# PGTNXEN_gate_out.net
KiCad netlist of a schematic drawn in EAGLE
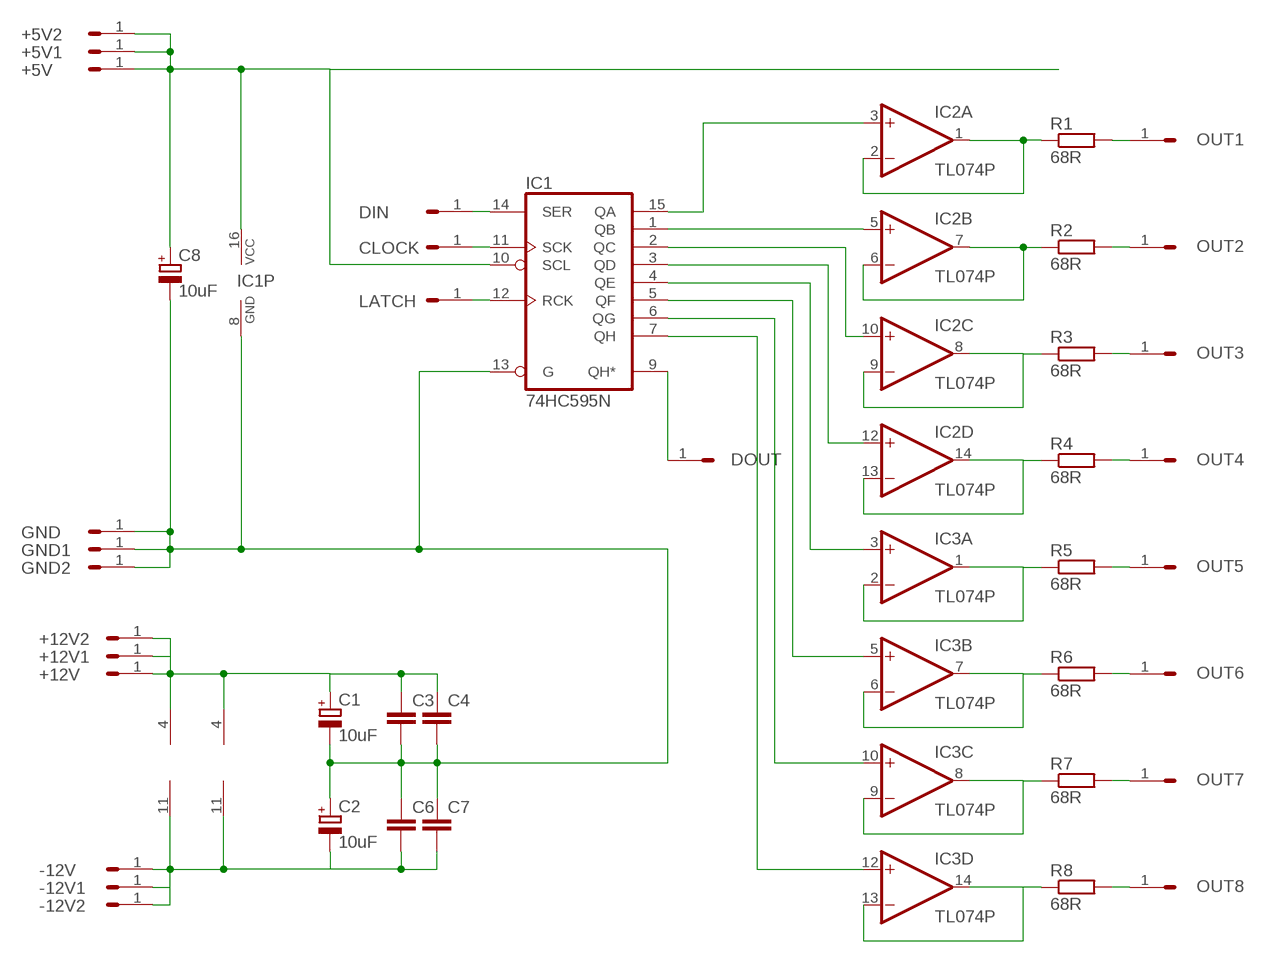
[diagram p0: schematic, sheet 1]

(export (version "E")
  (design (tool "Eeschema 10.0.6"))
  (components
    (comp (ref "+5V")
      (value "HEADER/MALE/01")
      (footprint "eagle-import:HEADER_MALE_01")
      (libsource (lib "eagle-import") (part "HEADER/MALE/01"))
    )
    (comp (ref "+5V1")
      (value "HEADER/MALE/01")
      (footprint "eagle-import:HEADER_MALE_01")
      (libsource (lib "eagle-import") (part "HEADER/MALE/01"))
    )
    (comp (ref "+5V2")
      (value "HEADER/MALE/01")
      (footprint "eagle-import:HEADER_MALE_01")
      (libsource (lib "eagle-import") (part "HEADER/MALE/01"))
    )
    (comp (ref "+12V")
      (value "HEADER/MALE/01")
      (footprint "eagle-import:HEADER_MALE_01")
      (libsource (lib "eagle-import") (part "HEADER/MALE/01"))
    )
    (comp (ref "+12V1")
      (value "HEADER/MALE/01")
      (footprint "eagle-import:HEADER_MALE_01")
      (libsource (lib "eagle-import") (part "HEADER/MALE/01"))
    )
    (comp (ref "+12V2")
      (value "HEADER/MALE/01")
      (footprint "eagle-import:HEADER_MALE_01")
      (libsource (lib "eagle-import") (part "HEADER/MALE/01"))
    )
    (comp (ref "-12V")
      (value "HEADER/MALE/01")
      (footprint "eagle-import:HEADER_MALE_01")
      (libsource (lib "eagle-import") (part "HEADER/MALE/01"))
    )
    (comp (ref "-12V1")
      (value "HEADER/MALE/01")
      (footprint "eagle-import:HEADER_MALE_01")
      (libsource (lib "eagle-import") (part "HEADER/MALE/01"))
    )
    (comp (ref "-12V2")
      (value "HEADER/MALE/01")
      (footprint "eagle-import:HEADER_MALE_01")
      (libsource (lib "eagle-import") (part "HEADER/MALE/01"))
    )
    (comp (ref "C1")
      (value "10uF")
      (footprint "eagle-import:E2,5-6")
      (libsource (lib "eagle-import") (part "CAPACITOR/POLARIZEDE2.5-6"))
    )
    (comp (ref "C2")
      (value "10uF")
      (footprint "eagle-import:E2,5-6")
      (libsource (lib "eagle-import") (part "CAPACITOR/POLARIZEDE2.5-6"))
    )
    (comp (ref "C3")
      (value "CAPACITORCERAMICDISC/5")
      (footprint "eagle-import:CERAMICDISC_5")
      (libsource (lib "eagle-import") (part "CAPACITORCERAMICDISC/5"))
    )
    (comp (ref "C4")
      (value "CAPACITORCERAMICDISC/5")
      (footprint "eagle-import:CERAMICDISC_5")
      (libsource (lib "eagle-import") (part "CAPACITORCERAMICDISC/5"))
    )
    (comp (ref "C6")
      (value "CAPACITORCERAMICDISC/5")
      (footprint "eagle-import:CERAMICDISC_5")
      (libsource (lib "eagle-import") (part "CAPACITORCERAMICDISC/5"))
    )
    (comp (ref "C7")
      (value "CAPACITORCERAMICDISC/5")
      (footprint "eagle-import:CERAMICDISC_5")
      (libsource (lib "eagle-import") (part "CAPACITORCERAMICDISC/5"))
    )
    (comp (ref "C8")
      (value "10uF")
      (footprint "eagle-import:E2,5-6")
      (libsource (lib "eagle-import") (part "CAPACITOR/POLARIZEDE2.5-6"))
    )
    (comp (ref "CLOCK")
      (value "HEADER/MALE/01")
      (footprint "eagle-import:HEADER_MALE_01")
      (libsource (lib "eagle-import") (part "HEADER/MALE/01"))
    )
    (comp (ref "DIN")
      (value "HEADER/MALE/01")
      (footprint "eagle-import:HEADER_MALE_01")
      (libsource (lib "eagle-import") (part "HEADER/MALE/01"))
    )
    (comp (ref "DOUT")
      (value "HEADER/MALE/01")
      (footprint "eagle-import:HEADER_MALE_01")
      (libsource (lib "eagle-import") (part "HEADER/MALE/01"))
    )
    (comp (ref "GND")
      (value "HEADER/MALE/01")
      (footprint "eagle-import:HEADER_MALE_01")
      (libsource (lib "eagle-import") (part "HEADER/MALE/01"))
    )
    (comp (ref "GND1")
      (value "HEADER/MALE/01")
      (footprint "eagle-import:HEADER_MALE_01")
      (libsource (lib "eagle-import") (part "HEADER/MALE/01"))
    )
    (comp (ref "GND2")
      (value "HEADER/MALE/01")
      (footprint "eagle-import:HEADER_MALE_01")
      (libsource (lib "eagle-import") (part "HEADER/MALE/01"))
    )
    (comp (ref "IC1")
      (value "74HC595N")
      (footprint "eagle-import:DIL16")
      (libsource (lib "eagle-import") (part "74595NHC"))
    )
    (comp (ref "IC2")
      (value "TL074P")
      (footprint "eagle-import:DIL14")
      (libsource (lib "eagle-import") (part "TL074P"))
    )
    (comp (ref "IC3")
      (value "TL074P")
      (footprint "eagle-import:DIL14")
      (libsource (lib "eagle-import") (part "TL074P"))
    )
    (comp (ref "LATCH")
      (value "HEADER/MALE/01")
      (footprint "eagle-import:HEADER_MALE_01")
      (libsource (lib "eagle-import") (part "HEADER/MALE/01"))
    )
    (comp (ref "OUT1")
      (value "HEADER/MALE/01")
      (footprint "eagle-import:HEADER_MALE_01")
      (libsource (lib "eagle-import") (part "HEADER/MALE/01"))
    )
    (comp (ref "OUT2")
      (value "HEADER/MALE/01")
      (footprint "eagle-import:HEADER_MALE_01")
      (libsource (lib "eagle-import") (part "HEADER/MALE/01"))
    )
    (comp (ref "OUT3")
      (value "HEADER/MALE/01")
      (footprint "eagle-import:HEADER_MALE_01")
      (libsource (lib "eagle-import") (part "HEADER/MALE/01"))
    )
    (comp (ref "OUT4")
      (value "HEADER/MALE/01")
      (footprint "eagle-import:HEADER_MALE_01")
      (libsource (lib "eagle-import") (part "HEADER/MALE/01"))
    )
    (comp (ref "OUT5")
      (value "HEADER/MALE/01")
      (footprint "eagle-import:HEADER_MALE_01")
      (libsource (lib "eagle-import") (part "HEADER/MALE/01"))
    )
    (comp (ref "OUT6")
      (value "HEADER/MALE/01")
      (footprint "eagle-import:HEADER_MALE_01")
      (libsource (lib "eagle-import") (part "HEADER/MALE/01"))
    )
    (comp (ref "OUT7")
      (value "HEADER/MALE/01")
      (footprint "eagle-import:HEADER_MALE_01")
      (libsource (lib "eagle-import") (part "HEADER/MALE/01"))
    )
    (comp (ref "OUT8")
      (value "HEADER/MALE/01")
      (footprint "eagle-import:HEADER_MALE_01")
      (libsource (lib "eagle-import") (part "HEADER/MALE/01"))
    )
    (comp (ref "R1")
      (value "68R")
      (footprint "eagle-import:RESISTOR_7.5")
      (libsource (lib "eagle-import") (part "RESISTORRESISTOR/UPRIGHT/7.5"))
    )
    (comp (ref "R2")
      (value "68R")
      (footprint "eagle-import:RESISTOR_7.5")
      (libsource (lib "eagle-import") (part "RESISTORRESISTOR/UPRIGHT/7.5"))
    )
    (comp (ref "R3")
      (value "68R")
      (footprint "eagle-import:RESISTOR_7.5")
      (libsource (lib "eagle-import") (part "RESISTORRESISTOR/UPRIGHT/7.5"))
    )
    (comp (ref "R4")
      (value "68R")
      (footprint "eagle-import:RESISTOR_7.5")
      (libsource (lib "eagle-import") (part "RESISTORRESISTOR/UPRIGHT/7.5"))
    )
    (comp (ref "R5")
      (value "68R")
      (footprint "eagle-import:RESISTOR_7.5")
      (libsource (lib "eagle-import") (part "RESISTORRESISTOR/UPRIGHT/7.5"))
    )
    (comp (ref "R6")
      (value "68R")
      (footprint "eagle-import:RESISTOR_7.5")
      (libsource (lib "eagle-import") (part "RESISTORRESISTOR/UPRIGHT/7.5"))
    )
    (comp (ref "R7")
      (value "68R")
      (footprint "eagle-import:RESISTOR_7.5")
      (libsource (lib "eagle-import") (part "RESISTORRESISTOR/UPRIGHT/7.5"))
    )
    (comp (ref "R8")
      (value "68R")
      (footprint "eagle-import:RESISTOR_7.5")
      (libsource (lib "eagle-import") (part "RESISTORRESISTOR/UPRIGHT/7.5"))
    )
  )
  (nets
    (net (code "1") (name "Net-(+5V-3)") (class "Default")
      (node (ref "+5V") (pin "1") (pinfunction "3_1") (pintype "passive"))
      (node (ref "+5V1") (pin "1") (pinfunction "3_1") (pintype "passive"))
      (node (ref "+5V2") (pin "1") (pinfunction "3_1") (pintype "passive"))
      (node (ref "C8") (pin "+") (pinfunction "+_+") (pintype "passive"))
      (node (ref "IC1") (pin "10") (pinfunction "SCL_10") (pintype "input"))
      (node (ref "IC1") (pin "16") (pinfunction "VCC_16") (pintype "power_in"))
    )
    (net (code "2") (name "Net-(+12V-3)") (class "Default")
      (node (ref "+12V") (pin "1") (pinfunction "3_1") (pintype "passive"))
      (node (ref "+12V1") (pin "1") (pinfunction "3_1") (pintype "passive"))
      (node (ref "+12V2") (pin "1") (pinfunction "3_1") (pintype "passive"))
      (node (ref "C1") (pin "+") (pinfunction "+_+") (pintype "passive"))
      (node (ref "C3") (pin "1") (pinfunction "1_1") (pintype "passive"))
      (node (ref "C4") (pin "1") (pinfunction "1_1") (pintype "passive"))
      (node (ref "IC2") (pin "4") (pinfunction "V+_4") (pintype "power_in"))
      (node (ref "IC3") (pin "4") (pinfunction "V+_4") (pintype "power_in"))
    )
    (net (code "3") (name "Net-(-12V-3)") (class "Default")
      (node (ref "-12V") (pin "1") (pinfunction "3_1") (pintype "passive"))
      (node (ref "-12V1") (pin "1") (pinfunction "3_1") (pintype "passive"))
      (node (ref "-12V2") (pin "1") (pinfunction "3_1") (pintype "passive"))
      (node (ref "C2") (pin "-") (pinfunction "-_-") (pintype "passive"))
      (node (ref "C6") (pin "2") (pinfunction "2_2") (pintype "passive"))
      (node (ref "C7") (pin "2") (pinfunction "2_2") (pintype "passive"))
      (node (ref "IC2") (pin "11") (pinfunction "V-_11") (pintype "power_in"))
      (node (ref "IC3") (pin "11") (pinfunction "V-_11") (pintype "power_in"))
    )
    (net (code "4") (name "Net-(CLOCK-3)") (class "Default")
      (node (ref "CLOCK") (pin "1") (pinfunction "3_1") (pintype "passive"))
      (node (ref "IC1") (pin "11") (pinfunction "SCK_11") (pintype "input"))
    )
    (net (code "5") (name "Net-(DIN-3)") (class "Default")
      (node (ref "DIN") (pin "1") (pinfunction "3_1") (pintype "passive"))
      (node (ref "IC1") (pin "14") (pinfunction "SER_14") (pintype "input"))
    )
    (net (code "6") (name "Net-(DOUT-3)") (class "Default")
      (node (ref "DOUT") (pin "1") (pinfunction "3_1") (pintype "passive"))
      (node (ref "IC1") (pin "9") (pinfunction "QH*_9") (pintype "tri_state"))
    )
    (net (code "7") (name "Net-(GND-3)") (class "Default")
      (node (ref "C1") (pin "-") (pinfunction "-_-") (pintype "passive"))
      (node (ref "C2") (pin "+") (pinfunction "+_+") (pintype "passive"))
      (node (ref "C3") (pin "2") (pinfunction "2_2") (pintype "passive"))
      (node (ref "C4") (pin "2") (pinfunction "2_2") (pintype "passive"))
      (node (ref "C6") (pin "1") (pinfunction "1_1") (pintype "passive"))
      (node (ref "C7") (pin "1") (pinfunction "1_1") (pintype "passive"))
      (node (ref "C8") (pin "-") (pinfunction "-_-") (pintype "passive"))
      (node (ref "GND") (pin "1") (pinfunction "3_1") (pintype "passive"))
      (node (ref "GND1") (pin "1") (pinfunction "3_1") (pintype "passive"))
      (node (ref "GND2") (pin "1") (pinfunction "3_1") (pintype "passive"))
      (node (ref "IC1") (pin "13") (pinfunction "G_13") (pintype "input"))
      (node (ref "IC1") (pin "8") (pinfunction "GND_8") (pintype "power_in"))
    )
    (net (code "8") (name "Net-(IC1A-QA)") (class "Default")
      (node (ref "IC1") (pin "15") (pinfunction "QA_15") (pintype "tri_state"))
      (node (ref "IC2") (pin "3") (pinfunction "+IN_3") (pintype "input"))
    )
    (net (code "9") (name "Net-(IC1A-QB)") (class "Default")
      (node (ref "IC1") (pin "1") (pinfunction "QB_1") (pintype "tri_state"))
      (node (ref "IC2") (pin "5") (pinfunction "+IN_5") (pintype "input"))
    )
    (net (code "10") (name "Net-(IC1A-QC)") (class "Default")
      (node (ref "IC1") (pin "2") (pinfunction "QC_2") (pintype "tri_state"))
      (node (ref "IC2") (pin "10") (pinfunction "+IN_10") (pintype "input"))
    )
    (net (code "11") (name "Net-(IC1A-QD)") (class "Default")
      (node (ref "IC1") (pin "3") (pinfunction "QD_3") (pintype "tri_state"))
      (node (ref "IC2") (pin "12") (pinfunction "+IN_12") (pintype "input"))
    )
    (net (code "12") (name "Net-(IC1A-QE)") (class "Default")
      (node (ref "IC1") (pin "4") (pinfunction "QE_4") (pintype "tri_state"))
      (node (ref "IC3") (pin "3") (pinfunction "+IN_3") (pintype "input"))
    )
    (net (code "13") (name "Net-(IC1A-QF)") (class "Default")
      (node (ref "IC1") (pin "5") (pinfunction "QF_5") (pintype "tri_state"))
      (node (ref "IC3") (pin "5") (pinfunction "+IN_5") (pintype "input"))
    )
    (net (code "14") (name "Net-(IC1A-QG)") (class "Default")
      (node (ref "IC1") (pin "6") (pinfunction "QG_6") (pintype "tri_state"))
      (node (ref "IC3") (pin "10") (pinfunction "+IN_10") (pintype "input"))
    )
    (net (code "15") (name "Net-(IC1A-QH)") (class "Default")
      (node (ref "IC1") (pin "7") (pinfunction "QH_7") (pintype "tri_state"))
      (node (ref "IC3") (pin "12") (pinfunction "+IN_12") (pintype "input"))
    )
    (net (code "16") (name "Net-(IC1A-RCK)") (class "Default")
      (node (ref "IC1") (pin "12") (pinfunction "RCK_12") (pintype "input"))
      (node (ref "LATCH") (pin "1") (pinfunction "3_1") (pintype "passive"))
    )
    (net (code "17") (name "Net-(IC2A--IN)") (class "Default")
      (node (ref "IC2") (pin "1") (pinfunction "OUT_1") (pintype "output"))
      (node (ref "IC2") (pin "2") (pinfunction "-IN_2") (pintype "input"))
      (node (ref "R1") (pin "1") (pinfunction "1_1") (pintype "passive"))
    )
    (net (code "18") (name "Net-(IC2B--IN)") (class "Default")
      (node (ref "IC2") (pin "6") (pinfunction "-IN_6") (pintype "input"))
      (node (ref "IC2") (pin "7") (pinfunction "OUT_7") (pintype "output"))
      (node (ref "R2") (pin "1") (pinfunction "1_1") (pintype "passive"))
    )
    (net (code "19") (name "Net-(IC2C--IN)") (class "Default")
      (node (ref "IC2") (pin "8") (pinfunction "OUT_8") (pintype "output"))
      (node (ref "IC2") (pin "9") (pinfunction "-IN_9") (pintype "input"))
      (node (ref "R3") (pin "1") (pinfunction "1_1") (pintype "passive"))
    )
    (net (code "20") (name "Net-(IC2D--IN)") (class "Default")
      (node (ref "IC2") (pin "13") (pinfunction "-IN_13") (pintype "input"))
      (node (ref "IC2") (pin "14") (pinfunction "OUT_14") (pintype "output"))
      (node (ref "R4") (pin "1") (pinfunction "1_1") (pintype "passive"))
    )
    (net (code "21") (name "Net-(IC3A--IN)") (class "Default")
      (node (ref "IC3") (pin "1") (pinfunction "OUT_1") (pintype "output"))
      (node (ref "IC3") (pin "2") (pinfunction "-IN_2") (pintype "input"))
      (node (ref "R5") (pin "1") (pinfunction "1_1") (pintype "passive"))
    )
    (net (code "22") (name "Net-(IC3B--IN)") (class "Default")
      (node (ref "IC3") (pin "6") (pinfunction "-IN_6") (pintype "input"))
      (node (ref "IC3") (pin "7") (pinfunction "OUT_7") (pintype "output"))
      (node (ref "R6") (pin "1") (pinfunction "1_1") (pintype "passive"))
    )
    (net (code "23") (name "Net-(IC3C--IN)") (class "Default")
      (node (ref "IC3") (pin "8") (pinfunction "OUT_8") (pintype "output"))
      (node (ref "IC3") (pin "9") (pinfunction "-IN_9") (pintype "input"))
      (node (ref "R7") (pin "1") (pinfunction "1_1") (pintype "passive"))
    )
    (net (code "24") (name "Net-(IC3D--IN)") (class "Default")
      (node (ref "IC3") (pin "13") (pinfunction "-IN_13") (pintype "input"))
      (node (ref "IC3") (pin "14") (pinfunction "OUT_14") (pintype "output"))
      (node (ref "R8") (pin "1") (pinfunction "1_1") (pintype "passive"))
    )
    (net (code "25") (name "Net-(OUT1-3)") (class "Default")
      (node (ref "OUT1") (pin "1") (pinfunction "3_1") (pintype "passive"))
      (node (ref "R1") (pin "2") (pinfunction "2_2") (pintype "passive"))
    )
    (net (code "26") (name "Net-(OUT2-3)") (class "Default")
      (node (ref "OUT2") (pin "1") (pinfunction "3_1") (pintype "passive"))
      (node (ref "R2") (pin "2") (pinfunction "2_2") (pintype "passive"))
    )
    (net (code "27") (name "Net-(OUT3-3)") (class "Default")
      (node (ref "OUT3") (pin "1") (pinfunction "3_1") (pintype "passive"))
      (node (ref "R3") (pin "2") (pinfunction "2_2") (pintype "passive"))
    )
    (net (code "28") (name "Net-(OUT4-3)") (class "Default")
      (node (ref "OUT4") (pin "1") (pinfunction "3_1") (pintype "passive"))
      (node (ref "R4") (pin "2") (pinfunction "2_2") (pintype "passive"))
    )
    (net (code "29") (name "Net-(OUT5-3)") (class "Default")
      (node (ref "OUT5") (pin "1") (pinfunction "3_1") (pintype "passive"))
      (node (ref "R5") (pin "2") (pinfunction "2_2") (pintype "passive"))
    )
    (net (code "30") (name "Net-(OUT6-3)") (class "Default")
      (node (ref "OUT6") (pin "1") (pinfunction "3_1") (pintype "passive"))
      (node (ref "R6") (pin "2") (pinfunction "2_2") (pintype "passive"))
    )
    (net (code "31") (name "Net-(OUT7-3)") (class "Default")
      (node (ref "OUT7") (pin "1") (pinfunction "3_1") (pintype "passive"))
      (node (ref "R7") (pin "2") (pinfunction "2_2") (pintype "passive"))
    )
    (net (code "32") (name "Net-(OUT8-3)") (class "Default")
      (node (ref "OUT8") (pin "1") (pinfunction "3_1") (pintype "passive"))
      (node (ref "R8") (pin "2") (pinfunction "2_2") (pintype "passive"))
    )
  )
)
